# V2.net
KiCad netlist of a schematic drawn in EasyEDA Pro
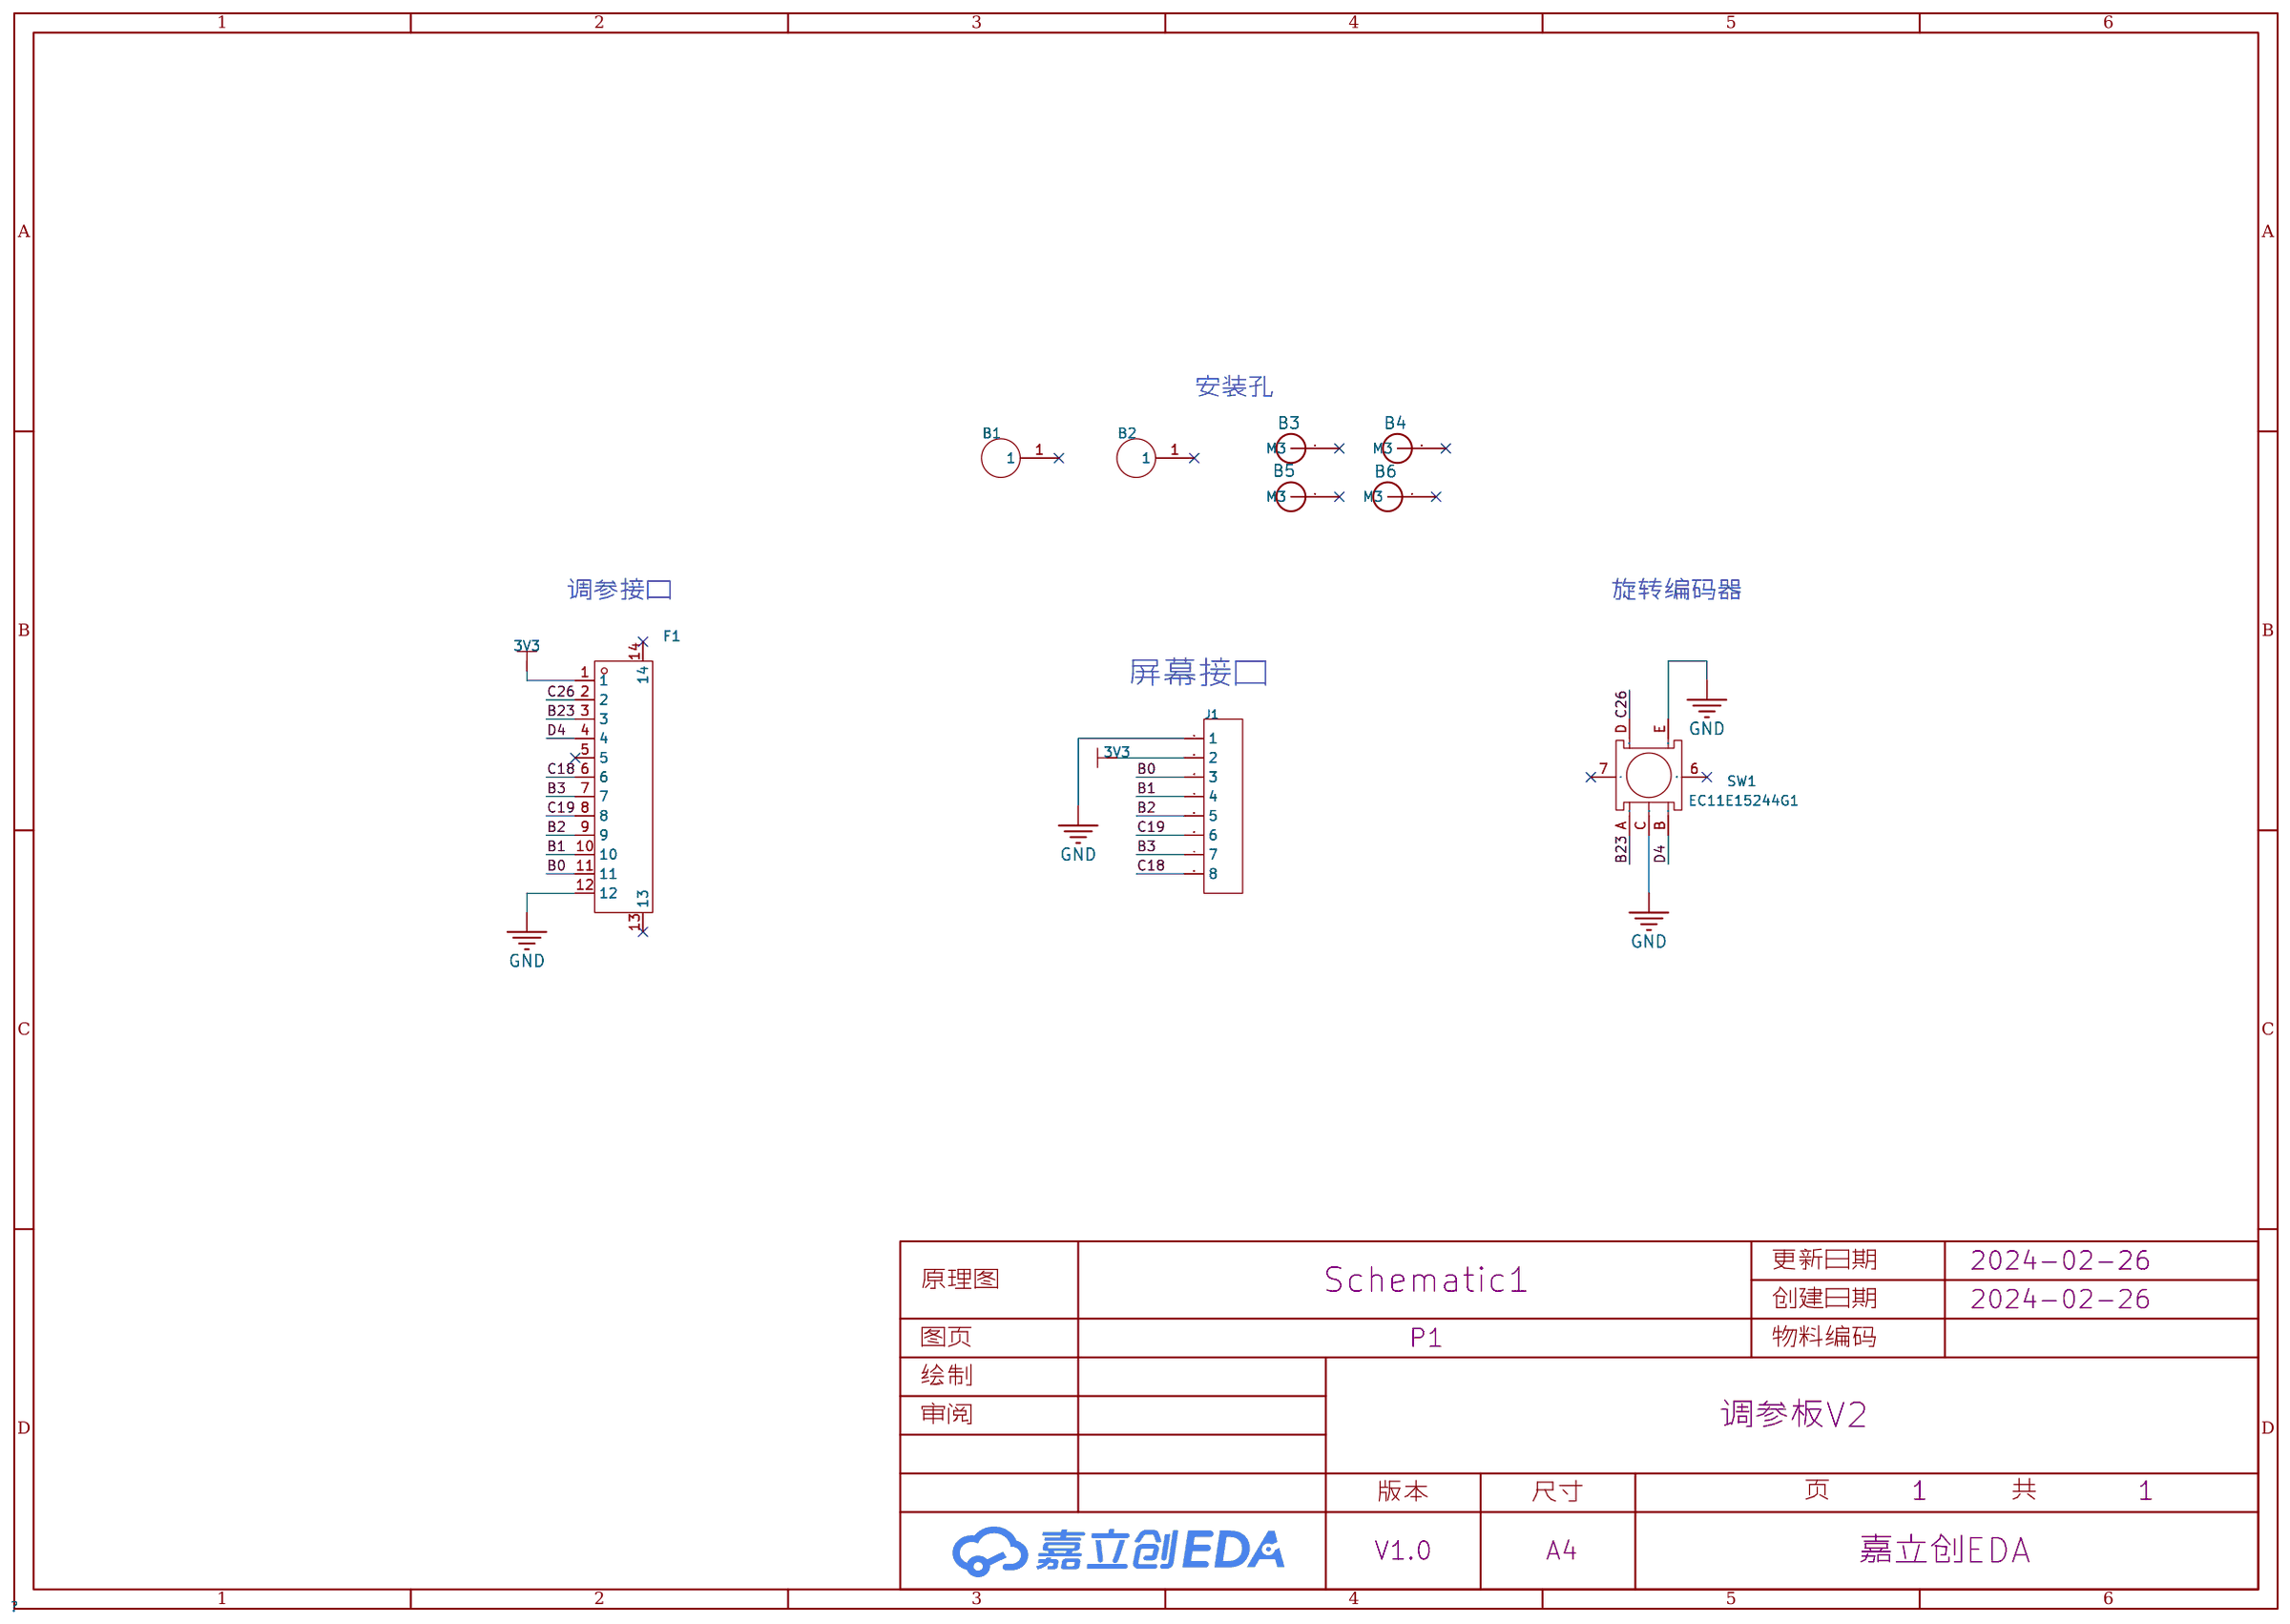
[diagram p0: schematic sheet]

(export (version "E")
  (design (tool "Eeschema 10.0.6"))
  (components
    (comp (ref "B1") (value "~") (footprint "easyedapro:M2") (libsource (lib "easyedapro") (part "M2")))
    (comp (ref "B2") (value "~") (footprint "easyedapro:M2") (libsource (lib "easyedapro") (part "M2")))
    (comp (ref "B3")
      (value "M3螺柱孔_JX")
      (footprint "easyedapro:M3")
      (libsource (lib "easyedapro") (part "M3螺柱孔_JX"))
    )
    (comp (ref "B4")
      (value "M3螺柱孔_JX")
      (footprint "easyedapro:M3")
      (libsource (lib "easyedapro") (part "M3螺柱孔_JX"))
    )
    (comp (ref "B5")
      (value "M3螺柱孔_JX")
      (footprint "easyedapro:M3")
      (libsource (lib "easyedapro") (part "M3螺柱孔_JX"))
    )
    (comp (ref "B6")
      (value "M3螺柱孔_JX")
      (footprint "easyedapro:M3")
      (libsource (lib "easyedapro") (part "M3螺柱孔_JX"))
    )
    (comp (ref "F1")
      (value "FPC-1.0FX-12PWCR-H20")
      (footprint "easyedapro:FPC-SMD_XUNPU_FPC-1.0FX-12PWCR-H20")
      (description "锁定特性:翻盖式;触点类型:下接;触点数量:12P;间距:1mm;安装类型:卧贴;")
      (fields (field (name "Manufacturer") "XUNPU(讯普)"))
      (libsource (lib "easyedapro") (part "FPC-1.0FX-12PWCR-H20"))
    )
    (comp (ref "J1")
      (value "~")
      (footprint "easyedapro:HDR-TH_8P-P2.54-V-F-1")
      (libsource (lib "easyedapro") (part "Header-Female-2.54_1x8"))
    )
    (comp (ref "SW1")
      (value "EC11E15244G1")
      (footprint "easyedapro:SW-TH_EC11E15244G1")
      (fields (field (name "Manufacturer") "ALPSALPINE(阿尔卑斯阿尔派)"))
      (libsource (lib "easyedapro") (part "EC11E15244G1"))
    )
  )
  (nets
    (net (code "1") (name "/B0") (class "Default")
      (node (ref "F1") (pin "11") (pinfunction "11_11") (pintype "unspecified"))
      (node (ref "J1") (pin "3") (pinfunction "3_3") (pintype "input"))
    )
    (net (code "2") (name "/B1") (class "Default")
      (node (ref "F1") (pin "10") (pinfunction "10_10") (pintype "unspecified"))
      (node (ref "J1") (pin "4") (pinfunction "4_4") (pintype "input"))
    )
    (net (code "3") (name "/B2") (class "Default")
      (node (ref "F1") (pin "9") (pinfunction "9_9") (pintype "unspecified"))
      (node (ref "J1") (pin "5") (pinfunction "5_5") (pintype "input"))
    )
    (net (code "4") (name "/B3") (class "Default")
      (node (ref "F1") (pin "7") (pinfunction "7_7") (pintype "unspecified"))
      (node (ref "J1") (pin "7") (pinfunction "7_7") (pintype "input"))
    )
    (net (code "5") (name "/B23") (class "Default")
      (node (ref "F1") (pin "3") (pinfunction "3_3") (pintype "unspecified"))
      (node (ref "SW1") (pin "A") (pinfunction "A_A") (pintype "unspecified"))
    )
    (net (code "6") (name "/C18") (class "Default")
      (node (ref "F1") (pin "6") (pinfunction "6_6") (pintype "unspecified"))
      (node (ref "J1") (pin "8") (pinfunction "8_8") (pintype "input"))
    )
    (net (code "7") (name "/C19") (class "Default")
      (node (ref "F1") (pin "8") (pinfunction "8_8") (pintype "unspecified"))
      (node (ref "J1") (pin "6") (pinfunction "6_6") (pintype "input"))
    )
    (net (code "8") (name "/C26") (class "Default")
      (node (ref "F1") (pin "2") (pinfunction "2_2") (pintype "unspecified"))
      (node (ref "SW1") (pin "D") (pinfunction "D_D") (pintype "unspecified"))
    )
    (net (code "9") (name "/D4") (class "Default")
      (node (ref "F1") (pin "4") (pinfunction "4_4") (pintype "unspecified"))
      (node (ref "SW1") (pin "B") (pinfunction "B_B") (pintype "unspecified"))
    )
    (net (code "10") (name "3V3") (class "Default")
      (node (ref "F1") (pin "1") (pinfunction "1_1") (pintype "unspecified"))
      (node (ref "J1") (pin "2") (pinfunction "2_2") (pintype "input"))
    )
    (net (code "11") (name "GND") (class "Default")
      (node (ref "F1") (pin "12") (pinfunction "12_12") (pintype "unspecified"))
      (node (ref "J1") (pin "1") (pinfunction "1_1") (pintype "input"))
      (node (ref "SW1") (pin "C") (pinfunction "C_C") (pintype "unspecified"))
      (node (ref "SW1") (pin "E") (pinfunction "E_E") (pintype "unspecified"))
    )
    (net (code "12") (name "unconnected-(B1-Pad1)") (class "Default")
      (node (ref "B1") (pin "1") (pinfunction "1_1") (pintype "input+no_connect"))
    )
    (net (code "13") (name "unconnected-(B2-Pad1)") (class "Default")
      (node (ref "B2") (pin "1") (pinfunction "1_1") (pintype "input+no_connect"))
    )
    (net (code "14") (name "unconnected-(B3-M3-Pad1)") (class "Default")
      (node (ref "B3") (pin "1") (pinfunction "M3_1") (pintype "input+no_connect"))
    )
    (net (code "15") (name "unconnected-(B4-M3-Pad1)") (class "Default")
      (node (ref "B4") (pin "1") (pinfunction "M3_1") (pintype "input+no_connect"))
    )
    (net (code "16") (name "unconnected-(B5-M3-Pad1)") (class "Default")
      (node (ref "B5") (pin "1") (pinfunction "M3_1") (pintype "input+no_connect"))
    )
    (net (code "17") (name "unconnected-(B6-M3-Pad1)") (class "Default")
      (node (ref "B6") (pin "1") (pinfunction "M3_1") (pintype "input+no_connect"))
    )
    (net (code "18") (name "unconnected-(F1-Pad5)") (class "Default")
      (node (ref "F1") (pin "5") (pinfunction "5_5") (pintype "unspecified+no_connect"))
    )
    (net (code "19") (name "unconnected-(F1-Pad13)") (class "Default")
      (node (ref "F1") (pin "13") (pinfunction "13_13") (pintype "unspecified+no_connect"))
    )
    (net (code "20") (name "unconnected-(F1-Pad14)") (class "Default")
      (node (ref "F1") (pin "14") (pinfunction "14_14") (pintype "unspecified+no_connect"))
    )
    (net (code "21") (name "unconnected-(SW1-Pad6)") (class "Default")
      (node (ref "SW1") (pin "6") (pinfunction "6_6") (pintype "unspecified+no_connect"))
    )
    (net (code "22") (name "unconnected-(SW1-Pad7)") (class "Default")
      (node (ref "SW1") (pin "7") (pinfunction "7_7") (pintype "unspecified+no_connect"))
    )
  )
)
